# BRD9057A_SiWx917M_4-Layer_ExtSw_REF_DES_.net
KiCad netlist of a schematic drawn in Altium Designer
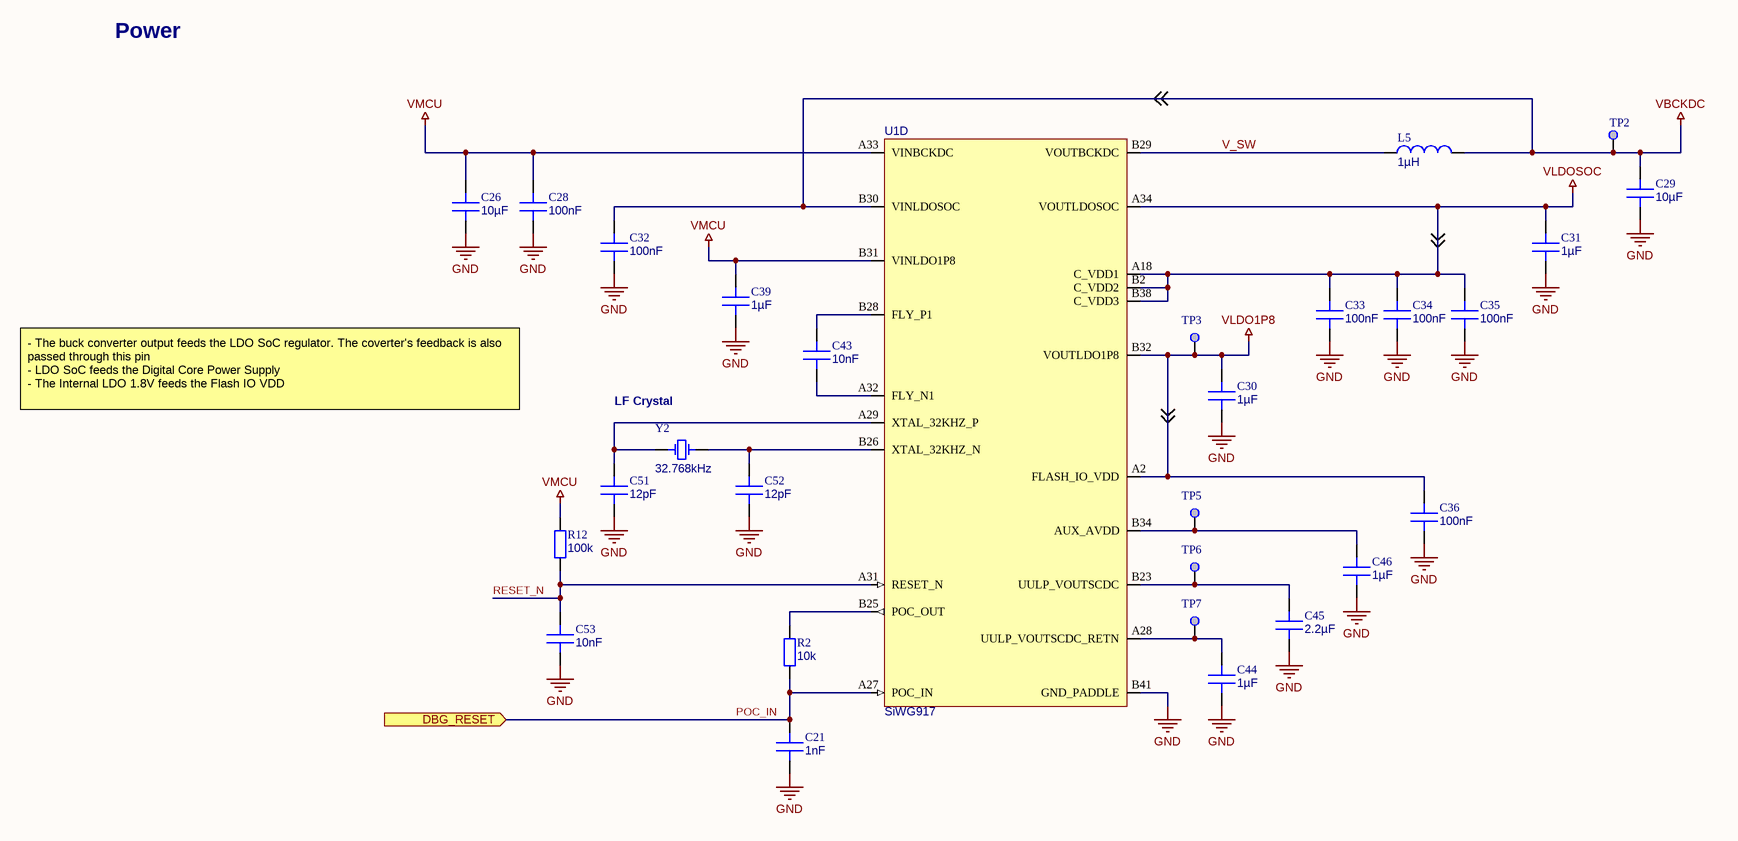
[diagram p0: BRD9057A_SiWx917M_4-Layer_ExtSw_REF_DES_A01_Page_3.SchDoc]

(export (version "E")
  (design (tool "Eeschema 10.0.6"))
  (components
    (comp (ref "C21")
      (value "1nF")
      (footprint "C0201_GM")
      (description "CAP CER 0201 X5R 1nF 16V 10%")
      (fields (field (name "TOLERANCE") "10%"))
      (libsource (lib "SiLabs Production Server") (part "Capacitor"))
    )
    (comp (ref "C26")
      (value "10µF")
      (footprint "C0603")
      (description "CAP CER 0603 X5R 10uF 16V 10%")
      (fields (field (name "TOLERANCE") "10%"))
      (libsource (lib "SiLabs Production Server") (part "Capacitor"))
    )
    (comp (ref "C28")
      (value "100nF")
      (footprint "C0201_GM")
      (description "CAP CER 0201 X5R 100nF 16V 10%")
      (fields (field (name "TOLERANCE") "10%"))
      (libsource (lib "SiLabs Production Server") (part "Capacitor"))
    )
    (comp (ref "C29")
      (value "10µF")
      (footprint "C0603")
      (description "CAP CER 0603 X5R 10uF 16V 10%")
      (fields (field (name "TOLERANCE") "10%"))
      (libsource (lib "SiLabs Production Server") (part "Capacitor"))
    )
    (comp (ref "C30")
      (value "1µF")
      (footprint "C0201_GM")
      (description "CAP CER 0201 X5R 1uF 16V 20%")
      (fields (field (name "TOLERANCE") "20%"))
      (libsource (lib "SiLabs Production Server") (part "Capacitor"))
    )
    (comp (ref "C31")
      (value "1µF")
      (footprint "C0201_GM")
      (description "CAP CER 0201 X5R 1uF 16V 20%")
      (fields (field (name "TOLERANCE") "20%"))
      (libsource (lib "SiLabs Production Server") (part "Capacitor"))
    )
    (comp (ref "C32")
      (value "100nF")
      (footprint "C0201_GM")
      (description "CAP CER 0201 X5R 100nF 16V 10%")
      (fields (field (name "TOLERANCE") "10%"))
      (libsource (lib "SiLabs Production Server") (part "Capacitor"))
    )
    (comp (ref "C33")
      (value "100nF")
      (footprint "C0201_GM")
      (description "CAP CER 0201 X5R 100nF 16V 10%")
      (fields (field (name "TOLERANCE") "10%"))
      (libsource (lib "SiLabs Production Server") (part "Capacitor"))
    )
    (comp (ref "C34")
      (value "100nF")
      (footprint "C0201_GM")
      (description "CAP CER 0201 X5R 100nF 16V 10%")
      (fields (field (name "TOLERANCE") "10%"))
      (libsource (lib "SiLabs Production Server") (part "Capacitor"))
    )
    (comp (ref "C35")
      (value "100nF")
      (footprint "C0201_GM")
      (description "CAP CER 0201 X5R 100nF 16V 10%")
      (fields (field (name "TOLERANCE") "10%"))
      (libsource (lib "SiLabs Production Server") (part "Capacitor"))
    )
    (comp (ref "C36")
      (value "100nF")
      (footprint "C0201_GM")
      (description "CAP CER 0201 X5R 100nF 16V 10%")
      (fields (field (name "TOLERANCE") "10%"))
      (libsource (lib "SiLabs Production Server") (part "Capacitor"))
    )
    (comp (ref "C39")
      (value "1µF")
      (footprint "C0201_GM")
      (description "CAP CER 0201 X5R 1uF 16V 20%")
      (fields (field (name "TOLERANCE") "20%"))
      (libsource (lib "SiLabs Production Server") (part "Capacitor"))
    )
    (comp (ref "C43")
      (value "10nF")
      (footprint "C0201_GM")
      (description "CAP CER 0201 X5R 10nF 16V 10%")
      (fields (field (name "TOLERANCE") "10%"))
      (libsource (lib "SiLabs Production Server") (part "Capacitor"))
    )
    (comp (ref "C44")
      (value "1µF")
      (footprint "C0201_GM")
      (description "CAP CER 0201 X5R 1uF 16V 20%")
      (fields (field (name "TOLERANCE") "20%"))
      (libsource (lib "SiLabs Production Server") (part "Capacitor"))
    )
    (comp (ref "C45")
      (value "2.2µF")
      (footprint "C0201_GM")
      (description "CAP CER 0201 X5R 2.2uF 10V 20%")
      (fields (field (name "TOLERANCE") "20%"))
      (libsource (lib "SiLabs Production Server") (part "Capacitor"))
    )
    (comp (ref "C46")
      (value "1µF")
      (footprint "C0201_GM")
      (description "CAP CER 0201 X5R 1uF 16V 20%")
      (fields (field (name "TOLERANCE") "20%"))
      (libsource (lib "SiLabs Production Server") (part "Capacitor"))
    )
    (comp (ref "C51")
      (value "12pF")
      (footprint "C0201_GM")
      (description "CAP CER 0201 C0G 12pF 50V 1%")
      (fields (field (name "TOLERANCE") "1%") (field (name "MANUFACTURER") "Murata"))
      (libsource (lib "SiLabs Production Server") (part "Capacitor"))
    )
    (comp (ref "C52")
      (value "12pF")
      (footprint "C0201_GM")
      (description "CAP CER 0201 C0G 12pF 50V 1%")
      (fields (field (name "TOLERANCE") "1%") (field (name "MANUFACTURER") "Murata"))
      (libsource (lib "SiLabs Production Server") (part "Capacitor"))
    )
    (comp (ref "C53")
      (value "10nF")
      (footprint "C0201_GM")
      (description "CAP CER 0201 X5R 10nF 16V 10%")
      (fields (field (name "TOLERANCE") "10%"))
      (libsource (lib "SiLabs Production Server") (part "Capacitor"))
    )
    (comp (ref "L5")
      (value "1µH")
      (footprint "INDC2012X100N_DFE")
      (description "IND Fixed 0805 1uH 2A 95mOhm 20%")
      (fields (field (name "MANUFACTURER") "Murata") (field (name "TOLERANCE") "20%"))
      (libsource (lib "SiLabs Production Server") (part "Inductor"))
    )
    (comp (ref "R2")
      (value "10k")
      (footprint "R0201")
      (description "RES 0201 10K 1/20W 1% 200ppm")
      (fields (field (name "TOLERANCE") "1%"))
      (libsource (lib "SiLabs Production Server") (part "Resistor"))
    )
    (comp (ref "R12")
      (value "100k")
      (footprint "R0201")
      (description "RES 0201 100K 1/20W 1% 200ppm")
      (fields (field (name "TOLERANCE") "1%"))
      (libsource (lib "SiLabs Production Server") (part "Resistor"))
    )
    (comp (ref "TP2")
      (value "TEST POINT SMD 1MM")
      (footprint "TP_1.0_SMD")
      (libsource (lib "SiLabs Production Server") (part "TEST POINT SMD"))
    )
    (comp (ref "TP3")
      (value "TEST POINT SMD 1MM")
      (footprint "TP_1.0_SMD")
      (libsource (lib "SiLabs Production Server") (part "TEST POINT SMD"))
    )
    (comp (ref "TP5")
      (value "TEST POINT SMD 1MM")
      (footprint "TP_1.0_SMD")
      (libsource (lib "SiLabs Production Server") (part "TEST POINT SMD"))
    )
    (comp (ref "TP6")
      (value "TEST POINT SMD 1MM")
      (footprint "TP_1.0_SMD")
      (libsource (lib "SiLabs Production Server") (part "TEST POINT SMD"))
    )
    (comp (ref "TP7")
      (value "TEST POINT SMD 1MM")
      (footprint "TP_1.0_SMD")
      (libsource (lib "SiLabs Production Server") (part "TEST POINT SMD"))
    )
    (comp (ref "U1")
      (value "SiWG917")
      (footprint "QFN84_SI_SiWx917_A1")
      (description "IC SoC 32BIT 8MB FLASH QFN84 2.4GHz Single Band Wi-Fi")
      (fields (field (name "MANUFACTURER") "Silicon Labs") (field (name "VOLTAGE") "3.63V"))
      (libsource (lib "SiLabs Production Server") (part "SiWx917"))
    )
    (comp (ref "Y2")
      (value "32.768kHz")
      (footprint "XTAL200X120X60-2N")
      (description "CRYSTAL 2.0x1.2mm 32.768kHz 7pF 20ppm")
      (fields (field (name "TOLERANCE") "20ppm") (field (name "MANUFACTURER") "Micro Crystal"))
      (libsource (lib "SiLabs Production Server") (part "XTAL-2P"))
    )
  )
  (nets
    (net (code "1") (name "/POC_IN") (class "Default")
      (node (ref "C21") (pin "2") (pinfunction "2_2") (pintype "passive"))
      (node (ref "R2") (pin "2") (pinfunction "2_2") (pintype "passive"))
      (node (ref "U1") (pin "A27") (pinfunction "POC_IN_A27") (pintype "input"))
    )
    (net (code "2") (name "/RESET_N") (class "Default")
      (node (ref "C53") (pin "2") (pinfunction "2_2") (pintype "passive"))
      (node (ref "R12") (pin "1") (pinfunction "1_1") (pintype "passive"))
      (node (ref "U1") (pin "A31") (pinfunction "RESET_N_A31") (pintype "input"))
    )
    (net (code "3") (name "/V_SW") (class "Default")
      (node (ref "L5") (pin "1") (pinfunction "1_1") (pintype "passive"))
      (node (ref "U1") (pin "B29") (pinfunction "VOUTBCKDC_B29") (pintype "power_in"))
    )
    (net (code "4") (name "GND") (class "Default")
      (node (ref "C21") (pin "1") (pinfunction "1_1") (pintype "passive"))
      (node (ref "C26") (pin "1") (pinfunction "1_1") (pintype "passive"))
      (node (ref "C28") (pin "1") (pinfunction "1_1") (pintype "passive"))
      (node (ref "C29") (pin "1") (pinfunction "1_1") (pintype "passive"))
      (node (ref "C30") (pin "1") (pinfunction "1_1") (pintype "passive"))
      (node (ref "C31") (pin "1") (pinfunction "1_1") (pintype "passive"))
      (node (ref "C32") (pin "1") (pinfunction "1_1") (pintype "passive"))
      (node (ref "C33") (pin "1") (pinfunction "1_1") (pintype "passive"))
      (node (ref "C34") (pin "1") (pinfunction "1_1") (pintype "passive"))
      (node (ref "C35") (pin "1") (pinfunction "1_1") (pintype "passive"))
      (node (ref "C36") (pin "1") (pinfunction "1_1") (pintype "passive"))
      (node (ref "C39") (pin "1") (pinfunction "1_1") (pintype "passive"))
      (node (ref "C44") (pin "1") (pinfunction "1_1") (pintype "passive"))
      (node (ref "C45") (pin "1") (pinfunction "1_1") (pintype "passive"))
      (node (ref "C46") (pin "1") (pinfunction "1_1") (pintype "passive"))
      (node (ref "C51") (pin "1") (pinfunction "1_1") (pintype "passive"))
      (node (ref "C52") (pin "1") (pinfunction "1_1") (pintype "passive"))
      (node (ref "C53") (pin "1") (pinfunction "1_1") (pintype "passive"))
      (node (ref "U1") (pin "B41") (pinfunction "GND_PADDLE_B41") (pintype "power_in"))
    )
    (net (code "5") (name "Net-(U1D-AUX_AVDD)") (class "Default")
      (node (ref "C46") (pin "2") (pinfunction "2_2") (pintype "passive"))
      (node (ref "TP5") (pin "1") (pinfunction "1_1") (pintype "passive"))
      (node (ref "U1") (pin "B34") (pinfunction "AUX_AVDD_B34") (pintype "power_in"))
    )
    (net (code "6") (name "Net-(U1D-FLY_N1)") (class "Default")
      (node (ref "C43") (pin "2") (pinfunction "2_2") (pintype "passive"))
      (node (ref "U1") (pin "A32") (pinfunction "FLY_N1_A32") (pintype "passive"))
    )
    (net (code "7") (name "Net-(U1D-FLY_P1)") (class "Default")
      (node (ref "C43") (pin "1") (pinfunction "1_1") (pintype "passive"))
      (node (ref "U1") (pin "B28") (pinfunction "FLY_P1_B28") (pintype "passive"))
    )
    (net (code "8") (name "Net-(U1D-POC_OUT)") (class "Default")
      (node (ref "R2") (pin "1") (pinfunction "1_1") (pintype "passive"))
      (node (ref "U1") (pin "B25") (pinfunction "POC_OUT_B25") (pintype "output"))
    )
    (net (code "9") (name "Net-(U1D-UULP_VOUTSCDC)") (class "Default")
      (node (ref "C45") (pin "2") (pinfunction "2_2") (pintype "passive"))
      (node (ref "TP6") (pin "1") (pinfunction "1_1") (pintype "passive"))
      (node (ref "U1") (pin "B23") (pinfunction "UULP_VOUTSCDC_B23") (pintype "power_in"))
    )
    (net (code "10") (name "Net-(U1D-UULP_VOUTSCDC_RETN)") (class "Default")
      (node (ref "C44") (pin "2") (pinfunction "2_2") (pintype "passive"))
      (node (ref "TP7") (pin "1") (pinfunction "1_1") (pintype "passive"))
      (node (ref "U1") (pin "A28") (pinfunction "UULP_VOUTSCDC_RETN_A28") (pintype "power_in"))
    )
    (net (code "11") (name "Net-(U1D-XTAL_32KHZ_N)") (class "Default")
      (node (ref "C52") (pin "2") (pinfunction "2_2") (pintype "passive"))
      (node (ref "U1") (pin "B26") (pinfunction "XTAL_32KHZ_N_B26") (pintype "passive"))
      (node (ref "Y2") (pin "1") (pinfunction "1_1") (pintype "passive"))
    )
    (net (code "12") (name "Net-(U1D-XTAL_32KHZ_P)") (class "Default")
      (node (ref "C51") (pin "2") (pinfunction "2_2") (pintype "passive"))
      (node (ref "U1") (pin "A29") (pinfunction "XTAL_32KHZ_P_A29") (pintype "passive"))
      (node (ref "Y2") (pin "2") (pinfunction "2_2") (pintype "passive"))
    )
    (net (code "13") (name "VBCKDC") (class "Default")
      (node (ref "C29") (pin "2") (pinfunction "2_2") (pintype "passive"))
      (node (ref "C32") (pin "2") (pinfunction "2_2") (pintype "passive"))
      (node (ref "L5") (pin "2") (pinfunction "2_2") (pintype "passive"))
      (node (ref "TP2") (pin "1") (pinfunction "1_1") (pintype "passive"))
      (node (ref "U1") (pin "B30") (pinfunction "VINLDOSOC_B30") (pintype "power_in"))
    )
    (net (code "14") (name "VLDO1P8") (class "Default")
      (node (ref "C30") (pin "2") (pinfunction "2_2") (pintype "passive"))
      (node (ref "C36") (pin "2") (pinfunction "2_2") (pintype "passive"))
      (node (ref "TP3") (pin "1") (pinfunction "1_1") (pintype "passive"))
      (node (ref "U1") (pin "A2") (pinfunction "FLASH_IO_VDD_A2") (pintype "power_in"))
      (node (ref "U1") (pin "B32") (pinfunction "VOUTLDO1P8_B32") (pintype "power_in"))
    )
    (net (code "15") (name "VLDOSOC") (class "Default")
      (node (ref "C31") (pin "2") (pinfunction "2_2") (pintype "passive"))
      (node (ref "C33") (pin "2") (pinfunction "2_2") (pintype "passive"))
      (node (ref "C34") (pin "2") (pinfunction "2_2") (pintype "passive"))
      (node (ref "C35") (pin "2") (pinfunction "2_2") (pintype "passive"))
      (node (ref "U1") (pin "A18") (pinfunction "C_VDD1_A18") (pintype "power_in"))
      (node (ref "U1") (pin "A34") (pinfunction "VOUTLDOSOC_A34") (pintype "power_in"))
      (node (ref "U1") (pin "B2") (pinfunction "C_VDD2_B2") (pintype "power_in"))
      (node (ref "U1") (pin "B38") (pinfunction "C_VDD3_B38") (pintype "power_in"))
    )
    (net (code "16") (name "VMCU") (class "Default")
      (node (ref "C26") (pin "2") (pinfunction "2_2") (pintype "passive"))
      (node (ref "C28") (pin "2") (pinfunction "2_2") (pintype "passive"))
      (node (ref "C39") (pin "2") (pinfunction "2_2") (pintype "passive"))
      (node (ref "R12") (pin "2") (pinfunction "2_2") (pintype "passive"))
      (node (ref "U1") (pin "A33") (pinfunction "VINBCKDC_A33") (pintype "power_in"))
      (node (ref "U1") (pin "B31") (pinfunction "VINLDO1P8_B31") (pintype "power_in"))
    )
  )
)
